# 2_Fuente.net
KiCad netlist of a schematic drawn in Altium Designer
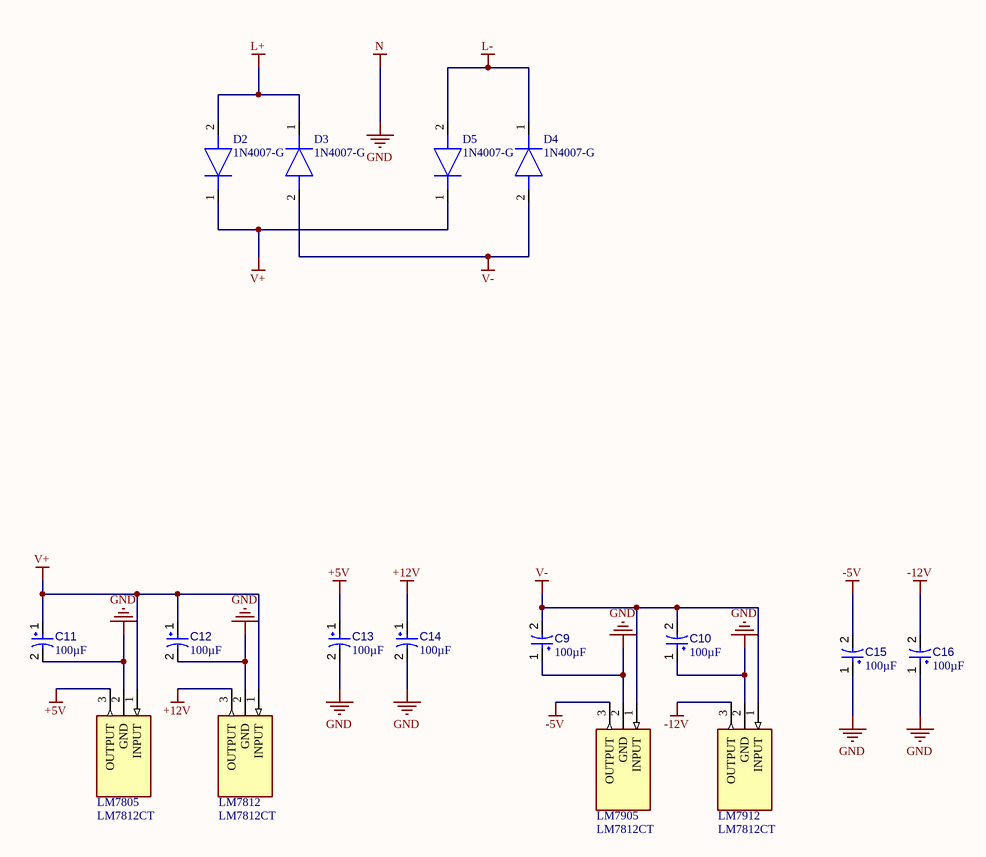
[diagram p0: 2_Fuente.SchDoc]

(export (version "E")
  (design (tool "Eeschema 10.0.6"))
  (components
    (comp (ref "C9")
      (value "100µF")
      (footprint "CAPPR55-200-1100X500X1200")
      (description "Aluminum Electrolytic Capacitor, 10 uF, +/- 20%, 50 V, -40 to 85 degC, 2-Pin THD, RoHS, Bulk")
      (fields (field (name "MANUFACTURER") "Panasonic") (field (name "TOLERANCE") "20%"))
      (libsource (lib "") (part "CAP-P-2_1"))
    )
    (comp (ref "C10")
      (value "100µF")
      (footprint "CAPPR55-200-1100X500X1200")
      (description "Aluminum Electrolytic Capacitor, 10 uF, +/- 20%, 50 V, -40 to 85 degC, 2-Pin THD, RoHS, Bulk")
      (fields (field (name "MANUFACTURER") "Panasonic") (field (name "TOLERANCE") "20%"))
      (libsource (lib "") (part "CAP-P-2_1"))
    )
    (comp (ref "C11")
      (value "100µF")
      (footprint "CAPPR55-200-1100X500X1200")
      (description "Aluminum Electrolytic Capacitor, 10 uF, +/- 20%, 50 V, -40 to 85 degC, 2-Pin THD, RoHS, Bulk")
      (fields (field (name "MANUFACTURER") "Panasonic") (field (name "TOLERANCE") "20%"))
      (libsource (lib "Universidad de Guadalajara") (part "CAP-P-2"))
    )
    (comp (ref "C12")
      (value "100µF")
      (footprint "CAPPR55-200-1100X500X1200")
      (description "Aluminum Electrolytic Capacitor, 10 uF, +/- 20%, 50 V, -40 to 85 degC, 2-Pin THD, RoHS, Bulk")
      (fields (field (name "MANUFACTURER") "Panasonic") (field (name "TOLERANCE") "20%"))
      (libsource (lib "Universidad de Guadalajara") (part "CAP-P-2"))
    )
    (comp (ref "C13")
      (value "100µF")
      (footprint "CAPPR55-200-1100X500X1200")
      (description "Aluminum Electrolytic Capacitor, 10 uF, +/- 20%, 50 V, -40 to 85 degC, 2-Pin THD, RoHS, Bulk")
      (fields (field (name "MANUFACTURER") "Panasonic") (field (name "TOLERANCE") "20%"))
      (libsource (lib "Universidad de Guadalajara") (part "CAP-P-2"))
    )
    (comp (ref "C14")
      (value "100µF")
      (footprint "CAPPR55-200-1100X500X1200")
      (description "Aluminum Electrolytic Capacitor, 10 uF, +/- 20%, 50 V, -40 to 85 degC, 2-Pin THD, RoHS, Bulk")
      (fields (field (name "MANUFACTURER") "Panasonic") (field (name "TOLERANCE") "20%"))
      (libsource (lib "Universidad de Guadalajara") (part "CAP-P-2"))
    )
    (comp (ref "C15")
      (value "100µF")
      (footprint "CAPPR55-200-1100X500X1200")
      (description "Aluminum Electrolytic Capacitor, 10 uF, +/- 20%, 50 V, -40 to 85 degC, 2-Pin THD, RoHS, Bulk")
      (fields (field (name "MANUFACTURER") "Panasonic") (field (name "TOLERANCE") "20%"))
      (libsource (lib "") (part "CAP-P-2_1"))
    )
    (comp (ref "C16")
      (value "100µF")
      (footprint "CAPPR55-200-1100X500X1200")
      (description "Aluminum Electrolytic Capacitor, 10 uF, +/- 20%, 50 V, -40 to 85 degC, 2-Pin THD, RoHS, Bulk")
      (fields (field (name "MANUFACTURER") "Panasonic") (field (name "TOLERANCE") "20%"))
      (libsource (lib "") (part "CAP-P-2_1"))
    )
    (comp (ref "D2")
      (value "1N4007-G")
      (footprint "SamacSys:DIOAD1410W90L470D235")
      (description "Diode")
      (fields (field (name "MOUSER PART NUMBER") "750-1N4007-G"))
      (libsource (lib "*") (part "1N4007-G"))
    )
    (comp (ref "D3")
      (value "1N4007-G")
      (footprint "SamacSys:DIOAD1410W90L470D235")
      (description "Diode")
      (fields (field (name "MOUSER PART NUMBER") "750-1N4007-G"))
      (libsource (lib "*") (part "1N4007-G"))
    )
    (comp (ref "D4")
      (value "1N4007-G")
      (footprint "SamacSys:DIOAD1410W90L470D235")
      (description "Diode")
      (fields (field (name "MOUSER PART NUMBER") "750-1N4007-G"))
      (libsource (lib "*") (part "1N4007-G"))
    )
    (comp (ref "D5")
      (value "1N4007-G")
      (footprint "SamacSys:DIOAD1410W90L470D235")
      (description "Diode")
      (fields (field (name "MOUSER PART NUMBER") "750-1N4007-G"))
      (libsource (lib "*") (part "1N4007-G"))
    )
    (comp (ref "LM7805")
      (value "LM7812CT")
      (footprint "SamacSys:TO254P470X1028X1955-3P")
      (description "Integrated Circuit")
      (fields (field (name "MOUSER PART NUMBER") "926-LM7812CT"))
      (libsource (lib "*") (part "LM7812CT"))
    )
    (comp (ref "LM7812")
      (value "LM7812CT")
      (footprint "SamacSys:TO254P470X1028X1955-3P")
      (description "Integrated Circuit")
      (fields (field (name "MOUSER PART NUMBER") "926-LM7812CT"))
      (libsource (lib "*") (part "LM7812CT"))
    )
    (comp (ref "LM7905")
      (value "LM7812CT")
      (footprint "SamacSys:TO254P470X1028X1955-3P")
      (description "Integrated Circuit")
      (fields (field (name "MOUSER PART NUMBER") "926-LM7812CT"))
      (libsource (lib "*") (part "LM7812CT"))
    )
    (comp (ref "LM7912")
      (value "LM7812CT")
      (footprint "SamacSys:TO254P470X1028X1955-3P")
      (description "Integrated Circuit")
      (fields (field (name "MOUSER PART NUMBER") "926-LM7812CT"))
      (libsource (lib "*") (part "LM7812CT"))
    )
  )
  (nets
    (net (code "1") (name "+5V") (class "Default")
      (node (ref "C13") (pin "1") (pinfunction "1_1") (pintype "passive"))
      (node (ref "LM7805") (pin "3") (pinfunction "OUTPUT_3") (pintype "output"))
    )
    (net (code "2") (name "+12V") (class "Default")
      (node (ref "C14") (pin "1") (pinfunction "1_1") (pintype "passive"))
      (node (ref "LM7812") (pin "3") (pinfunction "OUTPUT_3") (pintype "output"))
    )
    (net (code "3") (name "-5V") (class "Default")
      (node (ref "C15") (pin "2") (pinfunction "2_2") (pintype "passive"))
      (node (ref "LM7905") (pin "3") (pinfunction "OUTPUT_3") (pintype "output"))
    )
    (net (code "4") (name "-12V") (class "Default")
      (node (ref "C16") (pin "2") (pinfunction "2_2") (pintype "passive"))
      (node (ref "LM7912") (pin "3") (pinfunction "OUTPUT_3") (pintype "output"))
    )
    (net (code "5") (name "GND") (class "Default")
      (node (ref "C10") (pin "1") (pinfunction "1_1") (pintype "passive"))
      (node (ref "C11") (pin "2") (pinfunction "2_2") (pintype "passive"))
      (node (ref "C12") (pin "2") (pinfunction "2_2") (pintype "passive"))
      (node (ref "C13") (pin "2") (pinfunction "2_2") (pintype "passive"))
      (node (ref "C14") (pin "2") (pinfunction "2_2") (pintype "passive"))
      (node (ref "C15") (pin "1") (pinfunction "1_1") (pintype "passive"))
      (node (ref "C16") (pin "1") (pinfunction "1_1") (pintype "passive"))
      (node (ref "C9") (pin "1") (pinfunction "1_1") (pintype "passive"))
      (node (ref "LM7805") (pin "2") (pinfunction "GND_2") (pintype "power_in"))
      (node (ref "LM7812") (pin "2") (pinfunction "GND_2") (pintype "power_in"))
      (node (ref "LM7905") (pin "2") (pinfunction "GND_2") (pintype "power_in"))
      (node (ref "LM7912") (pin "2") (pinfunction "GND_2") (pintype "power_in"))
    )
    (net (code "6") (name "L+") (class "Default")
      (node (ref "D2") (pin "2") (pinfunction "A_2") (pintype "passive"))
      (node (ref "D3") (pin "1") (pinfunction "K_1") (pintype "passive"))
    )
    (net (code "7") (name "L-") (class "Default")
      (node (ref "D4") (pin "1") (pinfunction "K_1") (pintype "passive"))
      (node (ref "D5") (pin "2") (pinfunction "A_2") (pintype "passive"))
    )
    (net (code "8") (name "V+") (class "Default")
      (node (ref "C11") (pin "1") (pinfunction "1_1") (pintype "passive"))
      (node (ref "C12") (pin "1") (pinfunction "1_1") (pintype "passive"))
      (node (ref "D2") (pin "1") (pinfunction "K_1") (pintype "passive"))
      (node (ref "D5") (pin "1") (pinfunction "K_1") (pintype "passive"))
      (node (ref "LM7805") (pin "1") (pinfunction "INPUT_1") (pintype "input"))
      (node (ref "LM7812") (pin "1") (pinfunction "INPUT_1") (pintype "input"))
    )
    (net (code "9") (name "V-") (class "Default")
      (node (ref "C10") (pin "2") (pinfunction "2_2") (pintype "passive"))
      (node (ref "C9") (pin "2") (pinfunction "2_2") (pintype "passive"))
      (node (ref "D3") (pin "2") (pinfunction "A_2") (pintype "passive"))
      (node (ref "D4") (pin "2") (pinfunction "A_2") (pintype "passive"))
      (node (ref "LM7905") (pin "1") (pinfunction "INPUT_1") (pintype "input"))
      (node (ref "LM7912") (pin "1") (pinfunction "INPUT_1") (pintype "input"))
    )
  )
)
